# Std_12V.net
KiCad netlist of a schematic drawn in Altium Designer
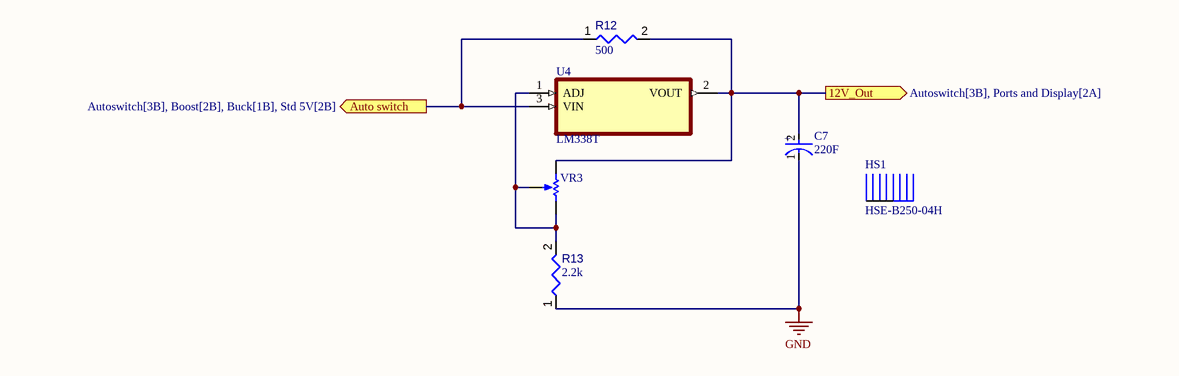
[diagram p0: Std 12V.SchDoc]

(export (version "E")
  (design (tool "Eeschema 10.0.6"))
  (components
    (comp (ref "C7")
      (value "220F")
      (footprint "FP-FTF-MFG")
      (fields (field (name "Comment") "Capacitors"))
      (libsource (lib "Vedant Ashtankar") (part "203bc49f2ac43e59fd269a8c329ed05"))
    )
    (comp (ref "HS1")
      (value "HSE-B250-04H")
      (footprint "HSINK_HSE-B250-04H")
      (description "Extruded Heat Sink, TO-220, 4 mm Vertical Solder Pin")
      (fields (field (name "MF") "Same Sky"))
      (libsource (lib "Vedant Ashtankar") (part "HSE-B250-04H"))
    )
    (comp (ref "R12")
      (value "500")
      (footprint "RESC0805(2012)_L")
      (description "1K 0.125W 5% 0805 (2012 Metric)  SMD")
      (fields (field (name "TOLERANCE") "5%") (field (name "POWER") "125mW"))
      (libsource (lib "Vedant Ashtankar") (part "1KR5J"))
    )
    (comp (ref "R13")
      (value "2.2k")
      (footprint "RESC0805(2012)_L")
      (description "1K 0.125W 5% 0805 (2012 Metric)  SMD")
      (fields (field (name "TOLERANCE") "5%") (field (name "POWER") "125mW"))
      (libsource (lib "Vedant Ashtankar") (part "1KR5J"))
    )
    (comp (ref "U4")
      (value "LM338T")
      (footprint "TO254P1054X470X1955-3")
      (description "5-A, 40-V, low-IQ, adjustable linear voltage regulator 3-TO-220 0 to 125")
      (fields (field (name "MF") "Texas Instruments"))
      (libsource (lib "Vedant Ashtankar") (part "LM338T"))
    )
    (comp (ref "VR3")
      (value "3362P-1-103LF")
      (footprint "BOUR-3362P")
      (description "Square Trimpot(R) Trimming Potentiometer, 10 KOhm, 300 V, -55 to 125 degC, 3-Pin THD, RoHS, Tube")
      (fields (field (name "MANUFACTURER") "Bourns") (field (name "TOLERANCE") "10%"))
      (libsource (lib "Vedant Ashtankar") (part "RES-POT-3"))
    )
  )
  (nets
    (net (code "1") (name "/12V_Out") (class "Default")
      (node (ref "C7") (pin "2") (pinfunction "A_2") (pintype "passive"))
      (node (ref "R12") (pin "2") (pinfunction "2_2") (pintype "passive"))
      (node (ref "U4") (pin "2") (pinfunction "VOUT_2") (pintype "output"))
      (node (ref "VR3") (pin "1") (pinfunction "CCW_1") (pintype "passive"))
    )
    (net (code "2") (name "/Auto switch") (class "Default")
      (node (ref "R12") (pin "1") (pinfunction "1_1") (pintype "passive"))
      (node (ref "U4") (pin "3") (pinfunction "VIN_3") (pintype "input"))
    )
    (net (code "3") (name "GND") (class "Default")
      (node (ref "C7") (pin "1") (pinfunction "C_1") (pintype "passive"))
      (node (ref "R13") (pin "1") (pinfunction "1_1") (pintype "passive"))
    )
    (net (code "4") (name "Net-(HS1-S-Pad1)") (class "Default")
      (node (ref "HS1") (pin "1") (pinfunction "S_1") (pintype "passive"))
      (node (ref "HS1") (pin "2") (pinfunction "S_2") (pintype "passive"))
    )
    (net (code "5") (name "Net-(U4-ADJ)") (class "Default")
      (node (ref "R13") (pin "2") (pinfunction "2_2") (pintype "passive"))
      (node (ref "U4") (pin "1") (pinfunction "ADJ_1") (pintype "input"))
      (node (ref "VR3") (pin "2") (pinfunction "S_2") (pintype "passive"))
      (node (ref "VR3") (pin "3") (pinfunction "CW_3") (pintype "passive"))
    )
  )
)
